# pyESP32.net
KiCad netlist of a schematic drawn in Altium Designer
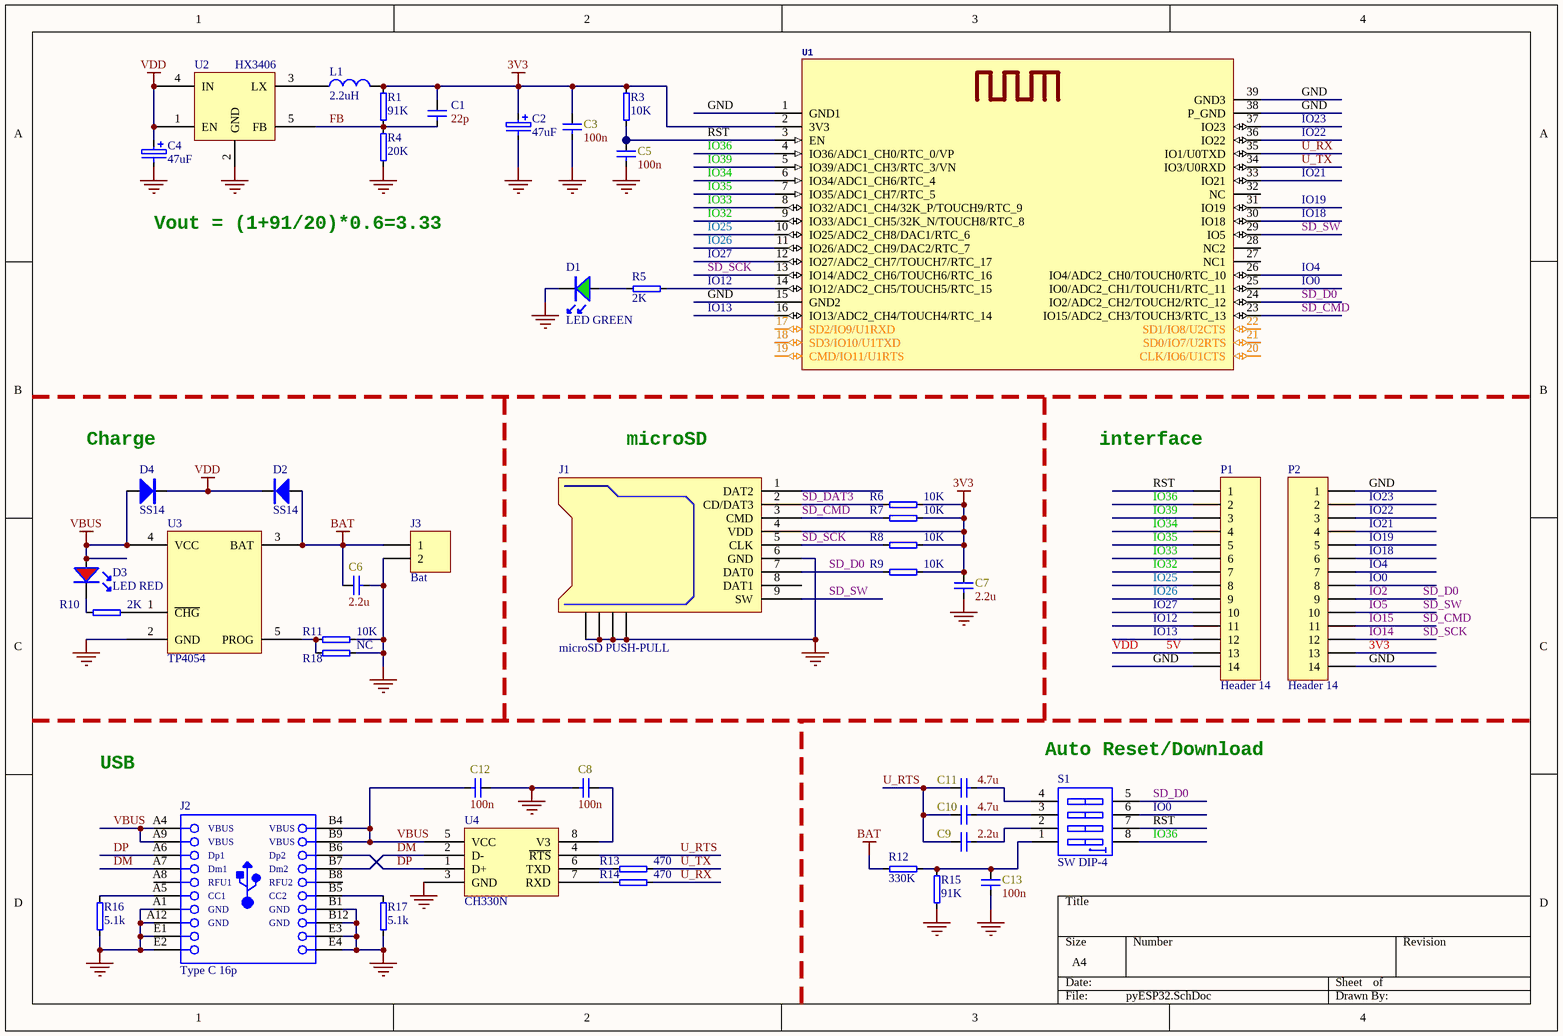
[diagram p0: pyESP32.SchDoc]

(export (version "E")
  (design (tool "Eeschema 10.0.6"))
  (components
    (comp (ref "C1") (value "22p") (footprint "C0402") (libsource (lib "s_device") (part "Cap")))
    (comp (ref "C2") (value "47uF") (footprint "3216") (libsource (lib "s_device") (part "E")))
    (comp (ref "C3") (value "100n") (footprint "C0402") (libsource (lib "s_device") (part "Cap")))
    (comp (ref "C4") (value "47uF") (footprint "3216") (libsource (lib "s_device") (part "E")))
    (comp (ref "C5") (value "100n") (footprint "C0402") (libsource (lib "s_device") (part "Cap")))
    (comp (ref "C6") (value "2.2u") (footprint "C0402") (libsource (lib "s_device") (part "Cap")))
    (comp (ref "C7") (value "2.2u") (footprint "C0402") (libsource (lib "s_device") (part "Cap")))
    (comp (ref "C8") (value "100n") (footprint "C0402") (libsource (lib "s_device") (part "Cap")))
    (comp (ref "C9") (value "2.2u") (footprint "C0402") (libsource (lib "s_device") (part "Cap")))
    (comp (ref "C10") (value "4.7u") (footprint "C0402") (libsource (lib "s_device") (part "Cap")))
    (comp (ref "C11") (value "4.7u") (footprint "C0402") (libsource (lib "s_device") (part "Cap")))
    (comp (ref "C12") (value "100n") (footprint "C0402") (libsource (lib "s_device") (part "Cap")))
    (comp (ref "C13") (value "100n") (footprint "C0402") (libsource (lib "s_device") (part "Cap")))
    (comp (ref "D1")
      (value "LED GREEN")
      (footprint "LED_0603_GREEN")
      (description "Green LED")
      (libsource (lib "s_device") (part "LED-GREEN"))
    )
    (comp (ref "D2") (value "SS14") (footprint "SOD-123") (libsource (lib "s_device") (part "Diode")))
    (comp (ref "D3")
      (value "LED RED")
      (footprint "LED_0603_RED")
      (description "RED LED")
      (libsource (lib "s_device") (part "LED-RED"))
    )
    (comp (ref "D4") (value "SS14") (footprint "SOD-123") (libsource (lib "s_device") (part "Diode")))
    (comp (ref "J1")
      (value "microSD PUSH-PULL")
      (footprint "microSD-1")
      (libsource (lib "s_device") (part "microSD PUSH-PULL"))
    )
    (comp (ref "J2")
      (value "Type C 16p")
      (footprint "Type-C 16P")
      (libsource (lib "s_connect") (part "Type C 16p"))
    )
    (comp (ref "J3")
      (value "Bat")
      (footprint "2P-1.25")
      (description "Header, 2-Pin")
      (fields (field (name "PUBLISHER") "Altium Limited"))
      (libsource (lib "s_connect") (part "Header 2"))
    )
    (comp (ref "L1")
      (value "2.2uH")
      (footprint "IND-252012")
      (fields (field (name "PUBLISHER") "Altium Limited"))
      (libsource (lib "s_device") (part "Inductor"))
    )
    (comp (ref "P1")
      (value "Header 14")
      (footprint "HDR1X14")
      (description "Header, 14-Pin")
      (fields (field (name "PUBLISHER") "Altium Limited"))
      (libsource (lib "Miscellaneous Connectors") (part "Header 14"))
    )
    (comp (ref "P2")
      (value "Header 14")
      (footprint "HDR1X14")
      (description "Header, 14-Pin")
      (fields (field (name "PUBLISHER") "Altium Limited"))
      (libsource (lib "") (part "Header 14_1"))
    )
    (comp (ref "R1") (value "91K") (footprint "SMD0402") (libsource (lib "s_device") (part "Res")))
    (comp (ref "R3") (value "10K") (footprint "SMD0402") (libsource (lib "s_device") (part "Res")))
    (comp (ref "R4") (value "20K") (footprint "SMD0402") (libsource (lib "s_device") (part "Res")))
    (comp (ref "R5") (value "2K") (footprint "SMD0402") (libsource (lib "s_device") (part "Res")))
    (comp (ref "R6") (value "10K") (footprint "SMD0402") (libsource (lib "s_device") (part "Res")))
    (comp (ref "R7") (value "10K") (footprint "SMD0402") (libsource (lib "s_device") (part "Res")))
    (comp (ref "R8") (value "10K") (footprint "SMD0402") (libsource (lib "s_device") (part "Res")))
    (comp (ref "R9") (value "10K") (footprint "SMD0402") (libsource (lib "s_device") (part "Res")))
    (comp (ref "R10") (value "2K") (footprint "SMD0402") (libsource (lib "s_device") (part "Res")))
    (comp (ref "R11") (value "10K") (footprint "SMD0402") (libsource (lib "s_device") (part "Res")))
    (comp (ref "R12") (value "330K") (footprint "SMD0402") (libsource (lib "s_device") (part "Res")))
    (comp (ref "R13") (value "470") (footprint "SMD0402") (libsource (lib "s_device") (part "Res")))
    (comp (ref "R14") (value "470") (footprint "SMD0402") (libsource (lib "s_device") (part "Res")))
    (comp (ref "R15") (value "91K") (footprint "SMD0402") (libsource (lib "s_device") (part "Res")))
    (comp (ref "R16") (value "5.1k") (footprint "SMD0402") (libsource (lib "s_device") (part "Res")))
    (comp (ref "R17") (value "5.1k") (footprint "SMD0402") (libsource (lib "s_device") (part "Res")))
    (comp (ref "R18") (value "NC") (footprint "SMD0402") (libsource (lib "s_device") (part "Res")))
    (comp (ref "S1")
      (value "SW DIP-4")
      (footprint "SW-SMD4")
      (description "DIP Switch, 4 Position, SPST")
      (fields (field (name "PUBLISHER") "Altium Limited"))
      (libsource (lib "s_device") (part "SW DIP-4"))
    )
    (comp (ref "U1")
      (value "ESP32-WROVER")
      (footprint "ESP32-WROVER")
      (libsource (lib "s_misc") (part "ESP32-WROVER"))
    )
    (comp (ref "U2") (value "HX3406") (footprint "SOT23-5") (libsource (lib "s_power") (part "SY8089")))
    (comp (ref "U3") (value "TP4054") (footprint "SOT23-5") (libsource (lib "s_power") (part "TP4054")))
    (comp (ref "U4") (value "CH330N") (footprint "NSO8_M") (libsource (lib "s_interface") (part "CH330N")))
  )
  (nets
    (net (code "1") (name "/DM") (class "Default")
      (node (ref "J2") (pin "A7") (pinfunction "Dm1_A7") (pintype "passive"))
      (node (ref "J2") (pin "B7") (pinfunction "Dm2_B7") (pintype "passive"))
      (node (ref "U4") (pin "2") (pinfunction "D-_2") (pintype "passive"))
    )
    (net (code "2") (name "/DP") (class "Default")
      (node (ref "J2") (pin "A6") (pinfunction "Dp1_A6") (pintype "passive"))
      (node (ref "J2") (pin "B6") (pinfunction "Dp2_B6") (pintype "passive"))
      (node (ref "U4") (pin "1") (pinfunction "D+_1") (pintype "passive"))
    )
    (net (code "3") (name "/FB") (class "Default")
      (node (ref "C1") (pin "1") (pintype "passive"))
      (node (ref "R1") (pin "1") (pintype "passive"))
      (node (ref "R4") (pin "2") (pintype "passive"))
      (node (ref "U2") (pin "5") (pinfunction "FB_5") (pintype "passive"))
    )
    (net (code "4") (name "/IO0") (class "Default")
      (node (ref "P2") (pin "8") (pinfunction "8_8") (pintype "passive"))
      (node (ref "S1") (pin "6") (pinfunction "B3_6") (pintype "passive"))
      (node (ref "U1") (pin "25") (pinfunction "IO0/ADC2_CH1/TOUCH1/RTC_11_25") (pintype "bidirectional"))
    )
    (net (code "5") (name "/IO2") (class "Default")
      (node (ref "J1") (pin "7") (pinfunction "DAT0_7") (pintype "passive"))
      (node (ref "P2") (pin "9") (pinfunction "9_9") (pintype "passive"))
      (node (ref "R9") (pin "2") (pintype "passive"))
      (node (ref "S1") (pin "5") (pinfunction "B4_5") (pintype "passive"))
      (node (ref "U1") (pin "24") (pinfunction "IO2/ADC2_CH2/TOUCH2/RTC_12_24") (pintype "bidirectional"))
    )
    (net (code "6") (name "/IO4") (class "Default")
      (node (ref "P2") (pin "7") (pinfunction "7_7") (pintype "passive"))
      (node (ref "U1") (pin "26") (pinfunction "IO4/ADC2_CH0/TOUCH0/RTC_10_26") (pintype "bidirectional"))
    )
    (net (code "7") (name "/IO5") (class "Default")
      (node (ref "J1") (pin "9") (pinfunction "SW_9") (pintype "passive"))
      (node (ref "P2") (pin "10") (pinfunction "10_10") (pintype "passive"))
      (node (ref "U1") (pin "29") (pinfunction "IO5_29") (pintype "bidirectional"))
    )
    (net (code "8") (name "/IO12") (class "Default")
      (node (ref "P1") (pin "11") (pinfunction "11_11") (pintype "passive"))
      (node (ref "R5") (pin "2") (pintype "passive"))
      (node (ref "U1") (pin "14") (pinfunction "IO12/ADC2_CH5/TOUCH5/RTC_15_14") (pintype "bidirectional"))
    )
    (net (code "9") (name "/IO13") (class "Default")
      (node (ref "P1") (pin "12") (pinfunction "12_12") (pintype "passive"))
      (node (ref "U1") (pin "16") (pinfunction "IO13/ADC2_CH4/TOUCH4/RTC_14_16") (pintype "bidirectional"))
    )
    (net (code "10") (name "/IO14") (class "Default")
      (node (ref "J1") (pin "5") (pinfunction "CLK_5") (pintype "passive"))
      (node (ref "P2") (pin "12") (pinfunction "12_12") (pintype "passive"))
      (node (ref "R8") (pin "2") (pintype "passive"))
      (node (ref "U1") (pin "13") (pinfunction "IO14/ADC2_CH6/TOUCH6/RTC_16_13") (pintype "bidirectional"))
    )
    (net (code "11") (name "/IO15") (class "Default")
      (node (ref "J1") (pin "3") (pinfunction "CMD_3") (pintype "passive"))
      (node (ref "P2") (pin "11") (pinfunction "11_11") (pintype "passive"))
      (node (ref "R7") (pin "2") (pintype "passive"))
      (node (ref "U1") (pin "23") (pinfunction "IO15/ADC2_CH3/TOUCH3/RTC_13_23") (pintype "bidirectional"))
    )
    (net (code "12") (name "/IO18") (class "Default")
      (node (ref "P2") (pin "6") (pinfunction "6_6") (pintype "passive"))
      (node (ref "U1") (pin "30") (pinfunction "IO18_30") (pintype "bidirectional"))
    )
    (net (code "13") (name "/IO19") (class "Default")
      (node (ref "P2") (pin "5") (pinfunction "5_5") (pintype "passive"))
      (node (ref "U1") (pin "31") (pinfunction "IO19_31") (pintype "bidirectional"))
    )
    (net (code "14") (name "/IO21") (class "Default")
      (node (ref "P2") (pin "4") (pinfunction "4_4") (pintype "passive"))
      (node (ref "U1") (pin "33") (pinfunction "IO21_33") (pintype "bidirectional"))
    )
    (net (code "15") (name "/IO22") (class "Default")
      (node (ref "P2") (pin "3") (pinfunction "3_3") (pintype "passive"))
      (node (ref "U1") (pin "36") (pinfunction "IO22_36") (pintype "bidirectional"))
    )
    (net (code "16") (name "/IO23") (class "Default")
      (node (ref "P2") (pin "2") (pinfunction "2_2") (pintype "passive"))
      (node (ref "U1") (pin "37") (pinfunction "IO23_37") (pintype "bidirectional"))
    )
    (net (code "17") (name "/IO25") (class "Default")
      (node (ref "P1") (pin "8") (pinfunction "8_8") (pintype "passive"))
      (node (ref "U1") (pin "10") (pinfunction "IO25/ADC2_CH8/DAC1/RTC_6_10") (pintype "bidirectional"))
    )
    (net (code "18") (name "/IO26") (class "Default")
      (node (ref "P1") (pin "9") (pinfunction "9_9") (pintype "passive"))
      (node (ref "U1") (pin "11") (pinfunction "IO26/ADC2_CH9/DAC2/RTC_7_11") (pintype "bidirectional"))
    )
    (net (code "19") (name "/IO27") (class "Default")
      (node (ref "P1") (pin "10") (pinfunction "10_10") (pintype "passive"))
      (node (ref "U1") (pin "12") (pinfunction "IO27/ADC2_CH7/TOUCH7/RTC_17_12") (pintype "bidirectional"))
    )
    (net (code "20") (name "/IO32") (class "Default")
      (node (ref "P1") (pin "7") (pinfunction "7_7") (pintype "passive"))
      (node (ref "U1") (pin "9") (pinfunction "IO33/ADC1_CH5/32K_N/TOUCH8/RTC_8_9") (pintype "bidirectional"))
    )
    (net (code "21") (name "/IO33") (class "Default")
      (node (ref "P1") (pin "6") (pinfunction "6_6") (pintype "passive"))
      (node (ref "U1") (pin "8") (pinfunction "IO32/ADC1_CH4/32K_P/TOUCH9/RTC_9_8") (pintype "bidirectional"))
    )
    (net (code "22") (name "/IO34") (class "Default")
      (node (ref "P1") (pin "4") (pinfunction "4_4") (pintype "passive"))
      (node (ref "U1") (pin "6") (pinfunction "IO34/ADC1_CH6/RTC_4_6") (pintype "input"))
    )
    (net (code "23") (name "/IO35") (class "Default")
      (node (ref "P1") (pin "5") (pinfunction "5_5") (pintype "passive"))
      (node (ref "U1") (pin "7") (pinfunction "IO35/ADC1_CH7/RTC_5_7") (pintype "input"))
    )
    (net (code "24") (name "/IO36") (class "Default")
      (node (ref "P1") (pin "2") (pinfunction "2_2") (pintype "passive"))
      (node (ref "S1") (pin "8") (pinfunction "B1_8") (pintype "passive"))
      (node (ref "U1") (pin "4") (pinfunction "IO36/ADC1_CH0/RTC_0/VP_4") (pintype "input"))
    )
    (net (code "25") (name "/IO39") (class "Default")
      (node (ref "P1") (pin "3") (pinfunction "3_3") (pintype "passive"))
      (node (ref "U1") (pin "5") (pinfunction "IO39/ADC1_CH3/RTC_3/VN_5") (pintype "input"))
    )
    (net (code "26") (name "/RST") (class "Default")
      (node (ref "C5") (pin "2") (pintype "passive"))
      (node (ref "P1") (pin "1") (pinfunction "1_1") (pintype "passive"))
      (node (ref "R3") (pin "1") (pintype "passive"))
      (node (ref "S1") (pin "7") (pinfunction "B2_7") (pintype "passive"))
      (node (ref "U1") (pin "3") (pinfunction "EN_3") (pintype "input"))
    )
    (net (code "27") (name "/SD_DAT3") (class "Default")
      (node (ref "J1") (pin "2") (pinfunction "CD/DAT3_2") (pintype "passive"))
      (node (ref "R6") (pin "2") (pintype "passive"))
    )
    (net (code "28") (name "/U_RTS") (class "Default")
      (node (ref "C10") (pin "2") (pintype "passive"))
      (node (ref "C11") (pin "2") (pintype "passive"))
      (node (ref "C9") (pin "2") (pintype "passive"))
      (node (ref "U4") (pin "4") (pinfunction "~{RTS}_4") (pintype "passive"))
    )
    (net (code "29") (name "/U_RX") (class "Default")
      (node (ref "R14") (pin "2") (pintype "passive"))
      (node (ref "U1") (pin "35") (pinfunction "IO1/U0TXD_35") (pintype "bidirectional"))
    )
    (net (code "30") (name "/U_TX") (class "Default")
      (node (ref "R13") (pin "2") (pintype "passive"))
      (node (ref "U1") (pin "34") (pinfunction "IO3/U0RXD_34") (pintype "bidirectional"))
    )
    (net (code "31") (name "3V3") (class "Default")
      (node (ref "C1") (pin "2") (pintype "passive"))
      (node (ref "C2") (pin "1") (pintype "passive"))
      (node (ref "C3") (pin "2") (pintype "passive"))
      (node (ref "C7") (pin "2") (pintype "passive"))
      (node (ref "J1") (pin "4") (pinfunction "VDD_4") (pintype "passive"))
      (node (ref "L1") (pin "2") (pinfunction "2_2") (pintype "passive"))
      (node (ref "P2") (pin "13") (pinfunction "13_13") (pintype "passive"))
      (node (ref "R1") (pin "2") (pintype "passive"))
      (node (ref "R3") (pin "2") (pintype "passive"))
      (node (ref "R6") (pin "1") (pintype "passive"))
      (node (ref "R7") (pin "1") (pintype "passive"))
      (node (ref "R8") (pin "1") (pintype "passive"))
      (node (ref "R9") (pin "1") (pintype "passive"))
      (node (ref "U1") (pin "2") (pinfunction "3V3_2") (pintype "power_in"))
    )
    (net (code "32") (name "BAT") (class "Default")
      (node (ref "C6") (pin "2") (pintype "passive"))
      (node (ref "D2") (pin "1") (pintype "passive"))
      (node (ref "J3") (pin "1") (pinfunction "1_1") (pintype "passive"))
      (node (ref "R12") (pin "2") (pintype "passive"))
      (node (ref "U3") (pin "3") (pinfunction "BAT_3") (pintype "passive"))
    )
    (net (code "33") (name "GND") (class "Default")
      (node (ref "C12") (pin "2") (pintype "passive"))
      (node (ref "C13") (pin "1") (pintype "passive"))
      (node (ref "C2") (pin "2") (pintype "passive"))
      (node (ref "C3") (pin "1") (pintype "passive"))
      (node (ref "C4") (pin "2") (pintype "passive"))
      (node (ref "C5") (pin "1") (pintype "passive"))
      (node (ref "C6") (pin "1") (pintype "passive"))
      (node (ref "C7") (pin "1") (pintype "passive"))
      (node (ref "C8") (pin "1") (pintype "passive"))
      (node (ref "D1") (pin "2") (pintype "passive"))
      (node (ref "J1") (pin "6") (pinfunction "GND_6") (pintype "passive"))
      (node (ref "J1") (pin "GP1") (pintype "passive"))
      (node (ref "J1") (pin "GP2") (pintype "passive"))
      (node (ref "J1") (pin "GP3") (pintype "passive"))
      (node (ref "J1") (pin "GP4") (pintype "passive"))
      (node (ref "J2") (pin "A1") (pinfunction "GND_A1") (pintype "passive"))
      (node (ref "J2") (pin "A12") (pinfunction "GND_A12") (pintype "passive"))
      (node (ref "J2") (pin "B1") (pinfunction "GND_B1") (pintype "passive"))
      (node (ref "J2") (pin "B12") (pinfunction "GND_B12") (pintype "passive"))
      (node (ref "J2") (pin "E1") (pinfunction "E1_E1") (pintype "passive"))
      (node (ref "J2") (pin "E2") (pintype "passive"))
      (node (ref "J2") (pin "E3") (pinfunction "E3_E3") (pintype "passive"))
      (node (ref "J2") (pin "E4") (pintype "passive"))
      (node (ref "J3") (pin "2") (pinfunction "2_2") (pintype "passive"))
      (node (ref "P1") (pin "14") (pinfunction "14_14") (pintype "passive"))
      (node (ref "P2") (pin "1") (pinfunction "1_1") (pintype "passive"))
      (node (ref "P2") (pin "14") (pinfunction "14_14") (pintype "passive"))
      (node (ref "R11") (pin "1") (pintype "passive"))
      (node (ref "R15") (pin "1") (pintype "passive"))
      (node (ref "R16") (pin "2") (pintype "passive"))
      (node (ref "R17") (pin "2") (pintype "passive"))
      (node (ref "R18") (pin "1") (pintype "passive"))
      (node (ref "R4") (pin "1") (pintype "passive"))
      (node (ref "U1") (pin "1") (pinfunction "GND1_1") (pintype "power_in"))
      (node (ref "U1") (pin "15") (pinfunction "GND2_15") (pintype "power_in"))
      (node (ref "U1") (pin "38") (pinfunction "P_GND_38") (pintype "power_in"))
      (node (ref "U1") (pin "39") (pinfunction "GND3_39") (pintype "power_in"))
      (node (ref "U2") (pin "2") (pinfunction "GND_2") (pintype "passive"))
      (node (ref "U3") (pin "2") (pinfunction "GND_2") (pintype "passive"))
      (node (ref "U4") (pin "3") (pinfunction "GND_3") (pintype "passive"))
    )
    (net (code "34") (name "Net-(D1-Pad1)") (class "Default")
      (node (ref "D1") (pin "1") (pintype "passive"))
      (node (ref "R5") (pin "1") (pintype "passive"))
    )
    (net (code "35") (name "Net-(D3-Pad2)") (class "Default")
      (node (ref "D3") (pin "2") (pintype "passive"))
      (node (ref "R10") (pin "2") (pintype "passive"))
    )
    (net (code "36") (name "Net-(J2-CC1)") (class "Default")
      (node (ref "J2") (pin "A5") (pinfunction "CC1_A5") (pintype "passive"))
      (node (ref "R16") (pin "1") (pintype "passive"))
    )
    (net (code "37") (name "Net-(J2-CC2)") (class "Default")
      (node (ref "J2") (pin "B5") (pinfunction "CC2_B5") (pintype "passive"))
      (node (ref "R17") (pin "1") (pintype "passive"))
    )
    (net (code "38") (name "Net-(S1-A1)") (class "Default")
      (node (ref "C13") (pin "2") (pintype "passive"))
      (node (ref "R12") (pin "1") (pintype "passive"))
      (node (ref "R15") (pin "2") (pintype "passive"))
      (node (ref "S1") (pin "1") (pinfunction "A1_1") (pintype "passive"))
    )
    (net (code "39") (name "Net-(S1-A2)") (class "Default")
      (node (ref "C9") (pin "1") (pintype "passive"))
      (node (ref "S1") (pin "2") (pinfunction "A2_2") (pintype "passive"))
    )
    (net (code "40") (name "Net-(S1-A3)") (class "Default")
      (node (ref "C10") (pin "1") (pintype "passive"))
      (node (ref "S1") (pin "3") (pinfunction "A3_3") (pintype "passive"))
    )
    (net (code "41") (name "Net-(S1-A4)") (class "Default")
      (node (ref "C11") (pin "1") (pintype "passive"))
      (node (ref "S1") (pin "4") (pinfunction "A4_4") (pintype "passive"))
    )
    (net (code "42") (name "Net-(U2-LX)") (class "Default")
      (node (ref "L1") (pin "1") (pinfunction "1_1") (pintype "passive"))
      (node (ref "U2") (pin "3") (pinfunction "LX_3") (pintype "passive"))
    )
    (net (code "43") (name "Net-(U3-PROG)") (class "Default")
      (node (ref "R11") (pin "2") (pintype "passive"))
      (node (ref "R18") (pin "2") (pintype "passive"))
      (node (ref "U3") (pin "5") (pinfunction "PROG_5") (pintype "passive"))
    )
    (net (code "44") (name "Net-(U3-~{CHG})") (class "Default")
      (node (ref "R10") (pin "1") (pintype "passive"))
      (node (ref "U3") (pin "1") (pinfunction "~{CHG}_1") (pintype "passive"))
    )
    (net (code "45") (name "Net-(U4-RXD)") (class "Default")
      (node (ref "R14") (pin "1") (pintype "passive"))
      (node (ref "U4") (pin "7") (pinfunction "RXD_7") (pintype "passive"))
    )
    (net (code "46") (name "Net-(U4-TXD)") (class "Default")
      (node (ref "R13") (pin "1") (pintype "passive"))
      (node (ref "U4") (pin "6") (pinfunction "TXD_6") (pintype "passive"))
    )
    (net (code "47") (name "Net-(U4-V3)") (class "Default")
      (node (ref "C8") (pin "2") (pintype "passive"))
      (node (ref "U4") (pin "8") (pinfunction "V3_8") (pintype "passive"))
    )
    (net (code "48") (name "VBUS") (class "Default")
      (node (ref "C12") (pin "1") (pintype "passive"))
      (node (ref "D3") (pin "1") (pintype "passive"))
      (node (ref "D4") (pin "1") (pintype "passive"))
      (node (ref "J2") (pin "A4") (pinfunction "VBUS_A4") (pintype "passive"))
      (node (ref "J2") (pin "A9") (pinfunction "VBUS_A9") (pintype "passive"))
      (node (ref "J2") (pin "B4") (pinfunction "VBUS_B4") (pintype "passive"))
      (node (ref "J2") (pin "B9") (pinfunction "VBUS_B9") (pintype "passive"))
      (node (ref "U3") (pin "4") (pinfunction "VCC_4") (pintype "passive"))
      (node (ref "U4") (pin "5") (pinfunction "VCC_5") (pintype "passive"))
    )
    (net (code "49") (name "VDD") (class "Default")
      (node (ref "C4") (pin "1") (pintype "passive"))
      (node (ref "D2") (pin "2") (pintype "passive"))
      (node (ref "D4") (pin "2") (pintype "passive"))
      (node (ref "P1") (pin "13") (pinfunction "13_13") (pintype "passive"))
      (node (ref "U2") (pin "1") (pinfunction "EN_1") (pintype "passive"))
      (node (ref "U2") (pin "4") (pinfunction "IN_4") (pintype "passive"))
    )
    (net (code "50") (name "unconnected-(J1-DAT1-Pad8)") (class "Default")
      (node (ref "J1") (pin "8") (pinfunction "DAT1_8") (pintype "passive"))
    )
    (net (code "51") (name "unconnected-(J1-DAT2-Pad1)") (class "Default")
      (node (ref "J1") (pin "1") (pinfunction "DAT2_1") (pintype "passive"))
    )
    (net (code "52") (name "unconnected-(J2-RFU1-PadA8)") (class "Default")
      (node (ref "J2") (pin "A8") (pinfunction "RFU1_A8") (pintype "passive"))
    )
    (net (code "53") (name "unconnected-(J2-RFU2-PadB8)") (class "Default")
      (node (ref "J2") (pin "B8") (pinfunction "RFU2_B8") (pintype "passive"))
    )
    (net (code "54") (name "unconnected-(U1-CLK{slash}IO6{slash}U1CTS-Pad20)") (class "Default")
      (node (ref "U1") (pin "20") (pinfunction "CLK/IO6/U1CTS_20") (pintype "bidirectional"))
    )
    (net (code "55") (name "unconnected-(U1-CMD{slash}IO11{slash}U1RTS-Pad19)") (class "Default")
      (node (ref "U1") (pin "19") (pinfunction "CMD/IO11/U1RTS_19") (pintype "bidirectional"))
    )
    (net (code "56") (name "unconnected-(U1-NC-Pad32)") (class "Default")
      (node (ref "U1") (pin "32") (pinfunction "NC_32") (pintype "passive"))
    )
    (net (code "57") (name "unconnected-(U1-NC1-Pad27)") (class "Default")
      (node (ref "U1") (pin "27") (pinfunction "NC1_27") (pintype "passive"))
    )
    (net (code "58") (name "unconnected-(U1-NC2-Pad28)") (class "Default")
      (node (ref "U1") (pin "28") (pinfunction "NC2_28") (pintype "passive"))
    )
    (net (code "59") (name "unconnected-(U1-SD0{slash}IO7{slash}U2RTS-Pad21)") (class "Default")
      (node (ref "U1") (pin "21") (pinfunction "SD0/IO7/U2RTS_21") (pintype "bidirectional"))
    )
    (net (code "60") (name "unconnected-(U1-SD1{slash}IO8{slash}U2CTS-Pad22)") (class "Default")
      (node (ref "U1") (pin "22") (pinfunction "SD1/IO8/U2CTS_22") (pintype "bidirectional"))
    )
    (net (code "61") (name "unconnected-(U1-SD2{slash}IO9{slash}U1RXD-Pad17)") (class "Default")
      (node (ref "U1") (pin "17") (pinfunction "SD2/IO9/U1RXD_17") (pintype "bidirectional"))
    )
    (net (code "62") (name "unconnected-(U1-SD3{slash}IO10{slash}U1TXD-Pad18)") (class "Default")
      (node (ref "U1") (pin "18") (pinfunction "SD3/IO10/U1TXD_18") (pintype "bidirectional"))
    )
  )
)
